# IP2315.net
KiCad netlist of a schematic drawn in Altium Designer
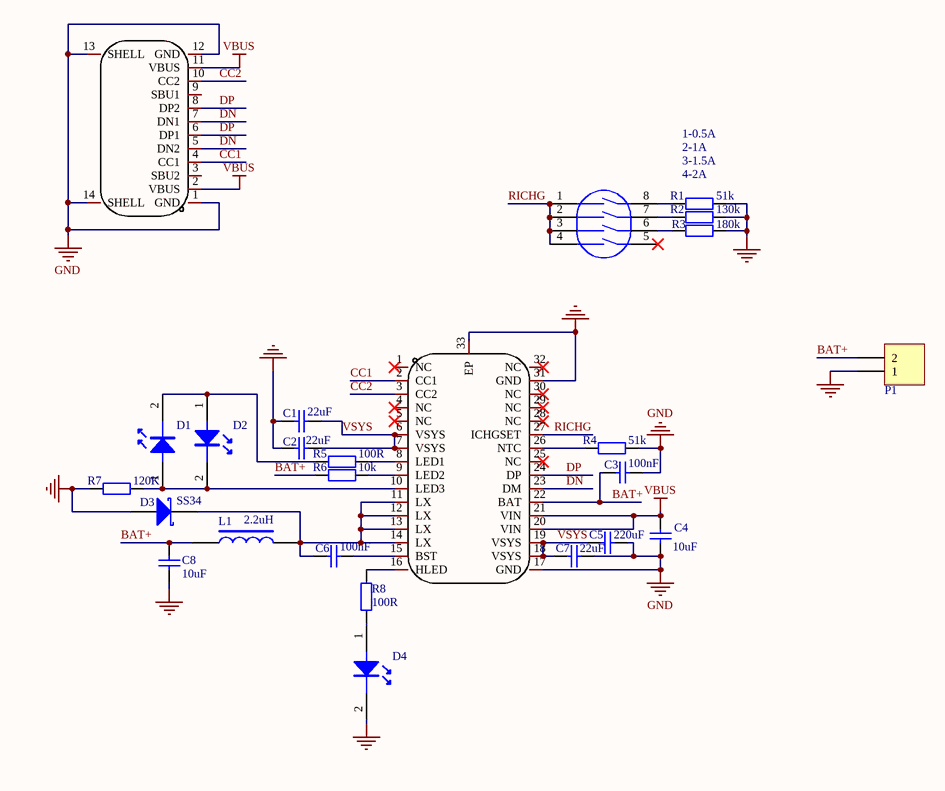
[diagram p0: IP2315.SchDoc]

(export (version "E")
  (design (tool "Eeschema 10.0.6"))
  (components
    (comp (ref "C1")
      (value "22uF")
      (footprint "0805C")
      (description "Capacitor")
      (fields (field (name "Comment") "Cap") (field (name "PUBLISHER") "Altium Limited"))
      (libsource (lib "CAMERON") (part "Cap_3"))
    )
    (comp (ref "C2")
      (value "22uF")
      (footprint "0805C")
      (description "Capacitor")
      (fields (field (name "Comment") "Cap") (field (name "PUBLISHER") "Altium Limited"))
      (libsource (lib "CAMERON") (part "Cap_3"))
    )
    (comp (ref "C3")
      (value "100nF")
      (footprint "C0603")
      (description "Capacitor")
      (fields (field (name "Comment") "Cap") (field (name "PUBLISHER") "Altium Limited"))
      (libsource (lib "CAMERON") (part "Cap_3"))
    )
    (comp (ref "C4")
      (value "10uF")
      (footprint "0805C")
      (description "Capacitor")
      (fields (field (name "Comment") "Cap") (field (name "PUBLISHER") "Altium Limited"))
      (libsource (lib "CAMERON") (part "Cap_3"))
    )
    (comp (ref "C5")
      (value "220uF")
      (footprint "CAP-SMD_BD6.3-L6.6-W6.6-LS7.4-FD")
      (description "Capacitor")
      (fields (field (name "Comment") "Cap") (field (name "PUBLISHER") "Altium Limited"))
      (libsource (lib "CAMERON") (part "Cap_3"))
    )
    (comp (ref "C6")
      (value "100nF")
      (footprint "C0603")
      (description "Capacitor")
      (fields (field (name "Comment") "Cap") (field (name "PUBLISHER") "Altium Limited"))
      (libsource (lib "CAMERON") (part "Cap_3"))
    )
    (comp (ref "C7")
      (value "22uF")
      (footprint "0805C")
      (description "Capacitor")
      (fields (field (name "Comment") "Cap") (field (name "PUBLISHER") "Altium Limited"))
      (libsource (lib "CAMERON") (part "Cap_3"))
    )
    (comp (ref "C8")
      (value "10uF")
      (footprint "0805C")
      (description "Capacitor")
      (fields (field (name "Comment") "Cap") (field (name "PUBLISHER") "Altium Limited"))
      (libsource (lib "CAMERON") (part "Cap_3"))
    )
    (comp (ref "D1") (value "Green") (footprint "LED0603-RD_RED") (libsource (lib "CAMERON") (part "LED")))
    (comp (ref "D2") (value "Green") (footprint "LED0603-RD_RED") (libsource (lib "CAMERON") (part "LED")))
    (comp (ref "D3")
      (value "SS34")
      (footprint "SMA_L4.3-W2.5-LS5.0-RD")
      (description "肖特基二极管")
      (libsource (lib "CAMERON") (part "SS34"))
    )
    (comp (ref "D4") (value "Green") (footprint "LED0603-RD_RED") (libsource (lib "CAMERON") (part "LED")))
    (comp (ref "L1")
      (value "2.2uH")
      (footprint "IND-SMD_L4.4-W4.2")
      (description "C167206")
      (libsource (lib "CAMERON") (part "INDUCTLR2_1"))
    )
    (comp (ref "P1")
      (value "VREF_SEL")
      (footprint "XH-2P-2.5")
      (description "Header, 2-Pin")
      (fields (field (name "PUBLISHER") "Altium Limited"))
      (libsource (lib "CAMERON") (part "Header 2"))
    )
    (comp (ref "R1")
      (value "51k")
      (footprint "R0603")
      (description "500mA")
      (fields (field (name "PUBLISHER") "Altium Limited"))
      (libsource (lib "") (part "Res2_1"))
    )
    (comp (ref "R2")
      (value "130k")
      (footprint "R0603")
      (description "Resistor")
      (fields (field (name "PUBLISHER") "Altium Limited"))
      (libsource (lib "") (part "Res2_1"))
    )
    (comp (ref "R3")
      (value "180k")
      (footprint "R0603")
      (description "Resistor")
      (fields (field (name "PUBLISHER") "Altium Limited"))
      (libsource (lib "") (part "Res2_1"))
    )
    (comp (ref "R4")
      (value "51k")
      (footprint "R0603")
      (description "500mA")
      (fields (field (name "PUBLISHER") "Altium Limited"))
      (libsource (lib "") (part "Res2_1"))
    )
    (comp (ref "R5")
      (value "100R")
      (footprint "R0603")
      (description "500mA")
      (fields (field (name "PUBLISHER") "Altium Limited"))
      (libsource (lib "") (part "Res2_1"))
    )
    (comp (ref "R6")
      (value "10k")
      (footprint "R0603")
      (description "500mA")
      (fields (field (name "PUBLISHER") "Altium Limited"))
      (libsource (lib "") (part "Res2_1"))
    )
    (comp (ref "R7")
      (value "120K")
      (footprint "R0603")
      (description "500mA")
      (fields (field (name "PUBLISHER") "Altium Limited"))
      (libsource (lib "") (part "Res2_1"))
    )
    (comp (ref "R8")
      (value "100R")
      (footprint "R0603")
      (description "500mA")
      (fields (field (name "PUBLISHER") "Altium Limited"))
      (libsource (lib "CAMERON") (part "Res2"))
    )
    (comp (ref "SW1")
      (value "DSHP04TS-S")
      (footprint "SW-SMD_8P-L6.7-W5.4-P1.27-LS8.5")
      (fields (field (name "MANUFACTURER") "XKB Connectivity(中国星坤)"))
      (libsource (lib "CAMERON") (part "DSHP04TS-S"))
    )
    (comp (ref "U1")
      (value "IP2315")
      (footprint "QFN-32_L5.0-W5.0-P0.50-BL-EP3.4")
      (fields (field (name "MANUFACTURER") "INJOINIC(英集芯)"))
      (libsource (lib "CAMERON") (part "IP2315"))
    )
    (comp (ref "USB1")
      (value "TYPE-C 16PIN 2MD(073)")
      (footprint "TYPE-C-16PIN-2MD-073")
      (fields (field (name "MANUFACTURER") "SHOU HAN(首韩)"))
      (libsource (lib "CAMERON") (part "TYPE-C 16PIN 2MD(073)"))
    )
  )
  (nets
    (net (code "1") (name "/BAT+") (class "Default")
      (node (ref "C3") (pin "2") (pinfunction "2_2") (pintype "passive"))
      (node (ref "C8") (pin "1") (pinfunction "1_1") (pintype "passive"))
      (node (ref "L1") (pin "1") (pinfunction "1_1") (pintype "passive"))
      (node (ref "P1") (pin "2") (pinfunction "2_2") (pintype "passive"))
      (node (ref "R6") (pin "1") (pinfunction "1_1") (pintype "passive"))
      (node (ref "U1") (pin "22") (pinfunction "BAT_22") (pintype "passive"))
    )
    (net (code "2") (name "/CC1") (class "Default")
      (node (ref "U1") (pin "2") (pinfunction "CC1_2") (pintype "passive"))
      (node (ref "USB1") (pin "4") (pinfunction "CC1_4") (pintype "passive"))
    )
    (net (code "3") (name "/CC2") (class "Default")
      (node (ref "U1") (pin "3") (pinfunction "CC2_3") (pintype "passive"))
      (node (ref "USB1") (pin "10") (pinfunction "CC2_10") (pintype "passive"))
    )
    (net (code "4") (name "/DN") (class "Default")
      (node (ref "U1") (pin "23") (pinfunction "DM_23") (pintype "passive"))
      (node (ref "USB1") (pin "5") (pinfunction "DN2_5") (pintype "passive"))
      (node (ref "USB1") (pin "7") (pinfunction "DN1_7") (pintype "passive"))
    )
    (net (code "5") (name "/DP") (class "Default")
      (node (ref "U1") (pin "24") (pinfunction "DP_24") (pintype "passive"))
      (node (ref "USB1") (pin "6") (pinfunction "DP1_6") (pintype "passive"))
      (node (ref "USB1") (pin "8") (pinfunction "DP2_8") (pintype "passive"))
    )
    (net (code "6") (name "/RICHG") (class "Default")
      (node (ref "SW1") (pin "1") (pinfunction "1_1") (pintype "passive"))
      (node (ref "SW1") (pin "2") (pinfunction "2_2") (pintype "passive"))
      (node (ref "SW1") (pin "3") (pinfunction "3_3") (pintype "passive"))
      (node (ref "SW1") (pin "4") (pinfunction "4_4") (pintype "passive"))
      (node (ref "U1") (pin "27") (pinfunction "ICHGSET_27") (pintype "passive"))
    )
    (net (code "7") (name "/VSYS") (class "Default")
      (node (ref "C1") (pin "1") (pinfunction "1_1") (pintype "passive"))
      (node (ref "C2") (pin "1") (pinfunction "1_1") (pintype "passive"))
      (node (ref "C5") (pin "2") (pinfunction "2_2") (pintype "passive"))
      (node (ref "C7") (pin "2") (pinfunction "2_2") (pintype "passive"))
      (node (ref "U1") (pin "18") (pinfunction "VSYS_18") (pintype "passive"))
      (node (ref "U1") (pin "19") (pinfunction "VSYS_19") (pintype "passive"))
      (node (ref "U1") (pin "6") (pinfunction "VSYS_6") (pintype "passive"))
      (node (ref "U1") (pin "7") (pinfunction "VSYS_7") (pintype "passive"))
    )
    (net (code "8") (name "GND") (class "Default")
      (node (ref "C1") (pin "2") (pinfunction "2_2") (pintype "passive"))
      (node (ref "C2") (pin "2") (pinfunction "2_2") (pintype "passive"))
      (node (ref "C3") (pin "1") (pinfunction "1_1") (pintype "passive"))
      (node (ref "C4") (pin "1") (pinfunction "1_1") (pintype "passive"))
      (node (ref "C5") (pin "1") (pinfunction "1_1") (pintype "passive"))
      (node (ref "C7") (pin "1") (pinfunction "1_1") (pintype "passive"))
      (node (ref "C8") (pin "2") (pinfunction "2_2") (pintype "passive"))
      (node (ref "D3") (pin "1") (pinfunction "A_1") (pintype "passive"))
      (node (ref "D4") (pin "2") (pinfunction "2_2") (pintype "passive"))
      (node (ref "P1") (pin "1") (pinfunction "1_1") (pintype "passive"))
      (node (ref "R1") (pin "2") (pinfunction "2_2") (pintype "passive"))
      (node (ref "R2") (pin "2") (pinfunction "2_2") (pintype "passive"))
      (node (ref "R3") (pin "2") (pinfunction "2_2") (pintype "passive"))
      (node (ref "R4") (pin "2") (pinfunction "2_2") (pintype "passive"))
      (node (ref "R7") (pin "1") (pinfunction "1_1") (pintype "passive"))
      (node (ref "U1") (pin "17") (pinfunction "GND_17") (pintype "passive"))
      (node (ref "U1") (pin "31") (pinfunction "GND_31") (pintype "passive"))
      (node (ref "U1") (pin "33") (pinfunction "EP_33") (pintype "passive"))
      (node (ref "USB1") (pin "1") (pinfunction "GND_1") (pintype "passive"))
      (node (ref "USB1") (pin "12") (pinfunction "GND_12") (pintype "passive"))
      (node (ref "USB1") (pin "13") (pinfunction "SHELL_13") (pintype "passive"))
      (node (ref "USB1") (pin "14") (pinfunction "SHELL_14") (pintype "passive"))
    )
    (net (code "9") (name "Net-(D1-Pad2)") (class "Default")
      (node (ref "D1") (pin "2") (pinfunction "2_2") (pintype "passive"))
      (node (ref "D2") (pin "1") (pinfunction "1_1") (pintype "passive"))
      (node (ref "R5") (pin "1") (pinfunction "1_1") (pintype "passive"))
    )
    (net (code "10") (name "Net-(D3-K)") (class "Default")
      (node (ref "C6") (pin "2") (pinfunction "2_2") (pintype "passive"))
      (node (ref "D3") (pin "2") (pinfunction "K_2") (pintype "passive"))
      (node (ref "L1") (pin "2") (pinfunction "2_2") (pintype "passive"))
      (node (ref "U1") (pin "11") (pinfunction "LX_11") (pintype "passive"))
      (node (ref "U1") (pin "12") (pinfunction "LX_12") (pintype "passive"))
      (node (ref "U1") (pin "13") (pinfunction "LX_13") (pintype "passive"))
      (node (ref "U1") (pin "14") (pinfunction "LX_14") (pintype "passive"))
    )
    (net (code "11") (name "Net-(D4-Pad1)") (class "Default")
      (node (ref "D4") (pin "1") (pinfunction "1_1") (pintype "passive"))
      (node (ref "R8") (pin "1") (pinfunction "1_1") (pintype "passive"))
    )
    (net (code "12") (name "Net-(R1-Pad1)") (class "Default")
      (node (ref "R1") (pin "1") (pinfunction "1_1") (pintype "passive"))
      (node (ref "SW1") (pin "8") (pinfunction "8_8") (pintype "passive"))
    )
    (net (code "13") (name "Net-(R2-Pad1)") (class "Default")
      (node (ref "R2") (pin "1") (pinfunction "1_1") (pintype "passive"))
      (node (ref "SW1") (pin "7") (pinfunction "7_7") (pintype "passive"))
    )
    (net (code "14") (name "Net-(R3-Pad1)") (class "Default")
      (node (ref "R3") (pin "1") (pinfunction "1_1") (pintype "passive"))
      (node (ref "SW1") (pin "6") (pinfunction "6_6") (pintype "passive"))
    )
    (net (code "15") (name "Net-(U1-BST)") (class "Default")
      (node (ref "C6") (pin "1") (pinfunction "1_1") (pintype "passive"))
      (node (ref "U1") (pin "15") (pinfunction "BST_15") (pintype "passive"))
    )
    (net (code "16") (name "Net-(U1-HLED)") (class "Default")
      (node (ref "R8") (pin "2") (pinfunction "2_2") (pintype "passive"))
      (node (ref "U1") (pin "16") (pinfunction "HLED_16") (pintype "passive"))
    )
    (net (code "17") (name "Net-(U1-LED1)") (class "Default")
      (node (ref "R5") (pin "2") (pinfunction "2_2") (pintype "passive"))
      (node (ref "U1") (pin "8") (pinfunction "LED1_8") (pintype "passive"))
    )
    (net (code "18") (name "Net-(U1-LED2)") (class "Default")
      (node (ref "R6") (pin "2") (pinfunction "2_2") (pintype "passive"))
      (node (ref "U1") (pin "9") (pinfunction "LED2_9") (pintype "passive"))
    )
    (net (code "19") (name "Net-(U1-LED3)") (class "Default")
      (node (ref "D1") (pin "1") (pinfunction "1_1") (pintype "passive"))
      (node (ref "D2") (pin "2") (pinfunction "2_2") (pintype "passive"))
      (node (ref "R7") (pin "2") (pinfunction "2_2") (pintype "passive"))
      (node (ref "U1") (pin "10") (pinfunction "LED3_10") (pintype "passive"))
    )
    (net (code "20") (name "Net-(U1-NTC)") (class "Default")
      (node (ref "R4") (pin "1") (pinfunction "1_1") (pintype "passive"))
      (node (ref "U1") (pin "26") (pinfunction "NTC_26") (pintype "passive"))
    )
    (net (code "21") (name "VBUS") (class "Default")
      (node (ref "C4") (pin "2") (pinfunction "2_2") (pintype "passive"))
      (node (ref "U1") (pin "20") (pinfunction "VIN_20") (pintype "passive"))
      (node (ref "U1") (pin "21") (pinfunction "VIN_21") (pintype "passive"))
      (node (ref "USB1") (pin "11") (pinfunction "VBUS_11") (pintype "passive"))
      (node (ref "USB1") (pin "2") (pinfunction "VBUS_2") (pintype "passive"))
    )
    (net (code "22") (name "unconnected-(SW1-Pad5)") (class "Default")
      (node (ref "SW1") (pin "5") (pinfunction "5_5") (pintype "passive+no_connect"))
    )
    (net (code "23") (name "unconnected-(U1-NC-Pad1)") (class "Default")
      (node (ref "U1") (pin "1") (pinfunction "NC_1") (pintype "passive+no_connect"))
    )
    (net (code "24") (name "unconnected-(U1-NC-Pad4)") (class "Default")
      (node (ref "U1") (pin "4") (pinfunction "NC_4") (pintype "passive+no_connect"))
    )
    (net (code "25") (name "unconnected-(U1-NC-Pad5)") (class "Default")
      (node (ref "U1") (pin "5") (pinfunction "NC_5") (pintype "passive+no_connect"))
    )
    (net (code "26") (name "unconnected-(U1-NC-Pad25)") (class "Default")
      (node (ref "U1") (pin "25") (pinfunction "NC_25") (pintype "passive+no_connect"))
    )
    (net (code "27") (name "unconnected-(U1-NC-Pad28)") (class "Default")
      (node (ref "U1") (pin "28") (pinfunction "NC_28") (pintype "passive+no_connect"))
    )
    (net (code "28") (name "unconnected-(U1-NC-Pad29)") (class "Default")
      (node (ref "U1") (pin "29") (pinfunction "NC_29") (pintype "passive+no_connect"))
    )
    (net (code "29") (name "unconnected-(U1-NC-Pad30)") (class "Default")
      (node (ref "U1") (pin "30") (pinfunction "NC_30") (pintype "passive+no_connect"))
    )
    (net (code "30") (name "unconnected-(U1-NC-Pad32)") (class "Default")
      (node (ref "U1") (pin "32") (pinfunction "NC_32") (pintype "passive+no_connect"))
    )
    (net (code "31") (name "unconnected-(USB1-SBU1-Pad9)") (class "Default")
      (node (ref "USB1") (pin "9") (pinfunction "SBU1_9") (pintype "passive"))
    )
    (net (code "32") (name "unconnected-(USB1-SBU2-Pad3)") (class "Default")
      (node (ref "USB1") (pin "3") (pinfunction "SBU2_3") (pintype "passive"))
    )
  )
)
